# Droon_REV3.net
KiCad netlist of a schematic drawn in Altium Designer
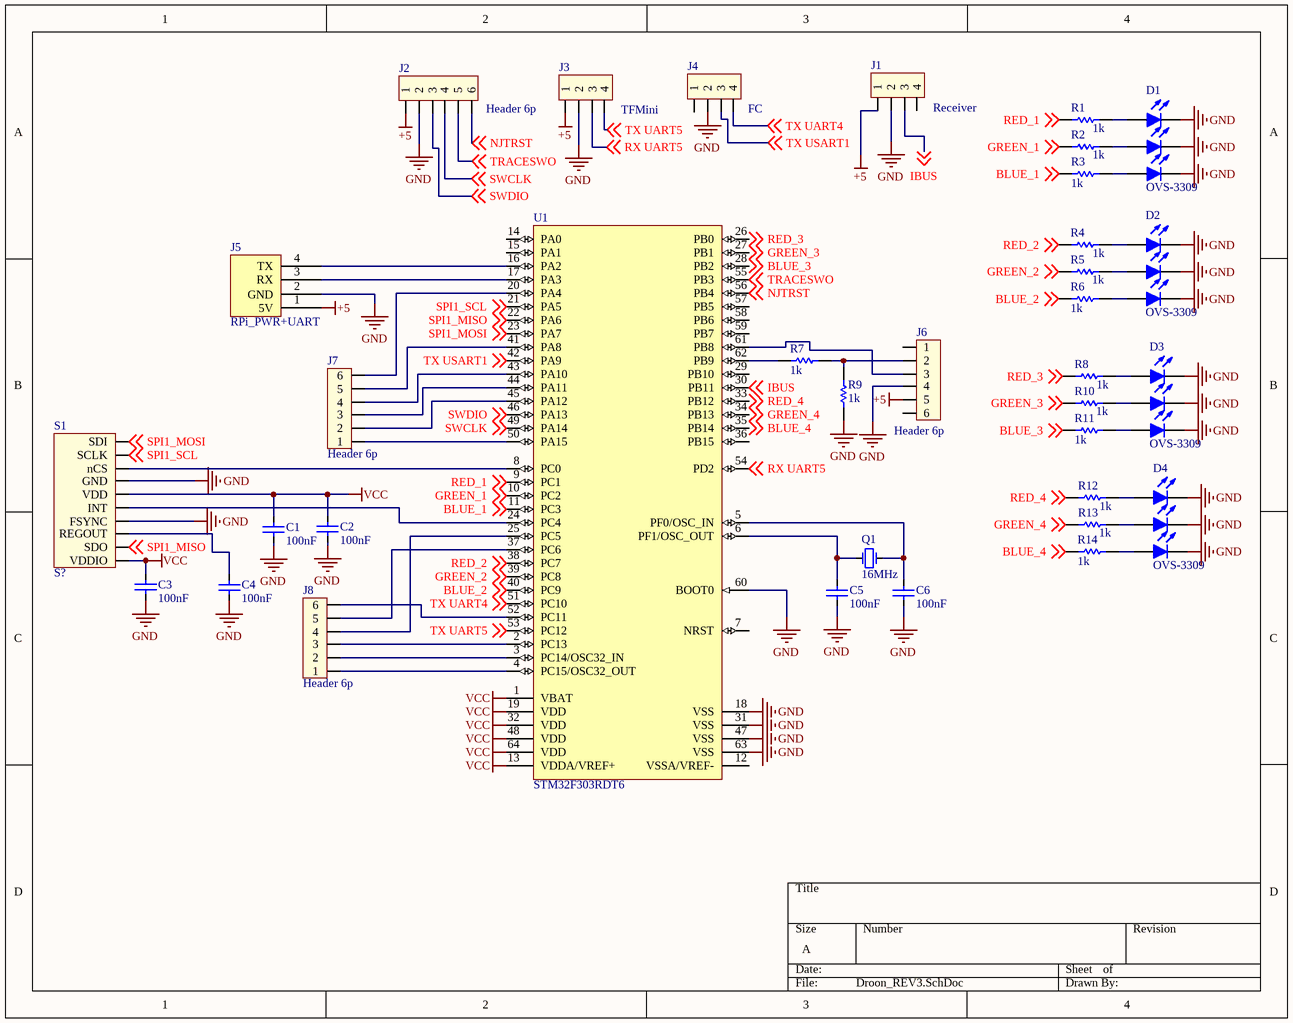
[diagram p0: Droon_REV3.SchDoc]

(export (version "E")
  (design (tool "Eeschema 10.0.6"))
  (components
    (comp (ref "C1")
      (value "100nF")
      (footprint "C0603")
      (description "Capacitor Ceramic")
      (libsource (lib "RK_Lib") (part "Capacitor"))
    )
    (comp (ref "C2")
      (value "100nF")
      (footprint "C0603")
      (description "Capacitor Ceramic")
      (libsource (lib "RK_Lib") (part "Capacitor"))
    )
    (comp (ref "C3")
      (value "100nF")
      (footprint "C0603")
      (description "Capacitor Ceramic")
      (libsource (lib "RK_Lib") (part "Capacitor"))
    )
    (comp (ref "C4")
      (value "100nF")
      (footprint "C0603")
      (description "Capacitor Ceramic")
      (libsource (lib "RK_Lib") (part "Capacitor"))
    )
    (comp (ref "C5")
      (value "100nF")
      (footprint "C0603")
      (description "Capacitor Ceramic")
      (libsource (lib "RK_Lib") (part "Capacitor"))
    )
    (comp (ref "C6")
      (value "100nF")
      (footprint "C0603")
      (description "Capacitor Ceramic")
      (libsource (lib "RK_Lib") (part "Capacitor"))
    )
    (comp (ref "D1")
      (value "OVS-3309")
      (footprint "LED RGB")
      (description "LED RGB")
      (libsource (lib "RK_Lib") (part "LED Tripple"))
    )
    (comp (ref "D2")
      (value "OVS-3309")
      (footprint "LED RGB")
      (description "LED RGB")
      (libsource (lib "RK_Lib") (part "LED Tripple"))
    )
    (comp (ref "D3")
      (value "OVS-3309")
      (footprint "LED RGB")
      (description "LED RGB")
      (libsource (lib "RK_Lib") (part "LED Tripple"))
    )
    (comp (ref "D4")
      (value "OVS-3309")
      (footprint "LED RGB")
      (description "LED RGB")
      (libsource (lib "RK_Lib") (part "LED Tripple"))
    )
    (comp (ref "J1")
      (value "Receiver")
      (footprint "JST-SH 4pin 1mm pitch")
      (libsource (lib "RK_Lib") (part "Header 4p"))
    )
    (comp (ref "J2")
      (value "Header 6p")
      (footprint "JST-SH 6pin 1mm pitch")
      (libsource (lib "") (part "Header 6p_2"))
    )
    (comp (ref "J3")
      (value "TFMini")
      (footprint "JST-SH 4pin 1mm pitch")
      (libsource (lib "RK_Lib") (part "Header 4p"))
    )
    (comp (ref "J4")
      (value "FC")
      (footprint "JST-SH 4pin 1mm pitch")
      (libsource (lib "RK_Lib") (part "Header 4p"))
    )
    (comp (ref "J5")
      (value "RPi_PWR+UART")
      (footprint "Header 2x20 2.54mm")
      (libsource (lib "RK_Lib") (part "RPi_PWR+UART"))
    )
    (comp (ref "J6")
      (value "Header 6p")
      (footprint "HEADER 6x1 2.54")
      (libsource (lib "") (part "Header 6p_3"))
    )
    (comp (ref "J7")
      (value "Header 6p")
      (footprint "JST-SH 6pin 1mm pitch")
      (libsource (lib "RK_Lib") (part "Header 6p"))
    )
    (comp (ref "J8")
      (value "Header 6p")
      (footprint "JST-SH 6pin 1mm pitch")
      (libsource (lib "") (part "Header 6p_1"))
    )
    (comp (ref "Q1")
      (value "16MHz")
      (footprint "Clock 2012\"(5032)")
      (description "Quarz crystal")
      (libsource (lib "RK_Lib") (part "Crystal"))
    )
    (comp (ref "R1")
      (value "1k")
      (footprint "R 0603")
      (description "Resistor")
      (libsource (lib "RK_Lib") (part "Res"))
    )
    (comp (ref "R2")
      (value "1k")
      (footprint "R 0603")
      (description "Resistor")
      (libsource (lib "RK_Lib") (part "Res"))
    )
    (comp (ref "R3")
      (value "1k")
      (footprint "R 0603")
      (description "Resistor")
      (libsource (lib "RK_Lib") (part "Res"))
    )
    (comp (ref "R4")
      (value "1k")
      (footprint "R 0603")
      (description "Resistor")
      (libsource (lib "RK_Lib") (part "Res"))
    )
    (comp (ref "R5")
      (value "1k")
      (footprint "R 0603")
      (description "Resistor")
      (libsource (lib "RK_Lib") (part "Res"))
    )
    (comp (ref "R6")
      (value "1k")
      (footprint "R 0603")
      (description "Resistor")
      (libsource (lib "RK_Lib") (part "Res"))
    )
    (comp (ref "R7")
      (value "1k")
      (footprint "R 0603")
      (description "Resistor")
      (libsource (lib "RK_Lib") (part "Res"))
    )
    (comp (ref "R8")
      (value "1k")
      (footprint "R 0603")
      (description "Resistor")
      (libsource (lib "RK_Lib") (part "Res"))
    )
    (comp (ref "R9")
      (value "1k")
      (footprint "R 0603")
      (description "Resistor")
      (libsource (lib "RK_Lib") (part "Res"))
    )
    (comp (ref "R10")
      (value "1k")
      (footprint "R 0603")
      (description "Resistor")
      (libsource (lib "RK_Lib") (part "Res"))
    )
    (comp (ref "R11")
      (value "1k")
      (footprint "R 0603")
      (description "Resistor")
      (libsource (lib "RK_Lib") (part "Res"))
    )
    (comp (ref "R12")
      (value "1k")
      (footprint "R 0603")
      (description "Resistor")
      (libsource (lib "RK_Lib") (part "Res"))
    )
    (comp (ref "R13")
      (value "1k")
      (footprint "R 0603")
      (description "Resistor")
      (libsource (lib "RK_Lib") (part "Res"))
    )
    (comp (ref "R14")
      (value "1k")
      (footprint "R 0603")
      (description "Resistor")
      (libsource (lib "RK_Lib") (part "Res"))
    )
    (comp (ref "S1")
      (value "S?")
      (footprint "IMU-ICM-20689")
      (libsource (lib "RK_Lib") (part "IMU_ICM-20689"))
    )
    (comp (ref "U1")
      (value "STM32F303RDT6")
      (footprint "LQFP64-STM32F303")
      (libsource (lib "RK_Lib") (part "LQFP64-STM32F303"))
    )
  )
  (nets
    (net (code "1") (name "+5") (class "Default")
      (node (ref "J1") (pin "1") (pinfunction "1_1") (pintype "passive"))
      (node (ref "J2") (pin "1") (pinfunction "1_1") (pintype "passive"))
      (node (ref "J3") (pin "1") (pinfunction "1_1") (pintype "passive"))
      (node (ref "J5") (pin "1") (pinfunction "5V_1") (pintype "passive"))
      (node (ref "J6") (pin "5") (pinfunction "5_5") (pintype "passive"))
    )
    (net (code "2") (name "BLUE_1") (class "Default")
      (node (ref "R3") (pin "1") (pinfunction "1_1") (pintype "passive"))
      (node (ref "U1") (pin "11") (pinfunction "PC3_11") (pintype "bidirectional"))
    )
    (net (code "3") (name "BLUE_2") (class "Default")
      (node (ref "R6") (pin "1") (pinfunction "1_1") (pintype "passive"))
      (node (ref "U1") (pin "40") (pinfunction "PC9_40") (pintype "bidirectional"))
    )
    (net (code "4") (name "BLUE_3") (class "Default")
      (node (ref "R11") (pin "1") (pinfunction "1_1") (pintype "passive"))
      (node (ref "U1") (pin "28") (pinfunction "PB2_28") (pintype "bidirectional"))
    )
    (net (code "5") (name "BLUE_4") (class "Default")
      (node (ref "R14") (pin "1") (pinfunction "1_1") (pintype "passive"))
      (node (ref "U1") (pin "35") (pinfunction "PB14_35") (pintype "bidirectional"))
    )
    (net (code "6") (name "GND") (class "Default")
      (node (ref "C1") (pin "1") (pinfunction "1_1") (pintype "passive"))
      (node (ref "C2") (pin "1") (pinfunction "1_1") (pintype "passive"))
      (node (ref "C3") (pin "1") (pinfunction "1_1") (pintype "passive"))
      (node (ref "C4") (pin "1") (pinfunction "1_1") (pintype "passive"))
      (node (ref "C5") (pin "1") (pinfunction "1_1") (pintype "passive"))
      (node (ref "C6") (pin "1") (pinfunction "1_1") (pintype "passive"))
      (node (ref "D1") (pin "BK") (pinfunction "BK_BK") (pintype "passive"))
      (node (ref "D1") (pin "GK") (pinfunction "GK_GK") (pintype "passive"))
      (node (ref "D1") (pin "RK") (pinfunction "RK_RK") (pintype "passive"))
      (node (ref "D2") (pin "BK") (pinfunction "BK_BK") (pintype "passive"))
      (node (ref "D2") (pin "GK") (pinfunction "GK_GK") (pintype "passive"))
      (node (ref "D2") (pin "RK") (pinfunction "RK_RK") (pintype "passive"))
      (node (ref "D3") (pin "BK") (pinfunction "BK_BK") (pintype "passive"))
      (node (ref "D3") (pin "GK") (pinfunction "GK_GK") (pintype "passive"))
      (node (ref "D3") (pin "RK") (pinfunction "RK_RK") (pintype "passive"))
      (node (ref "D4") (pin "BK") (pinfunction "BK_BK") (pintype "passive"))
      (node (ref "D4") (pin "GK") (pinfunction "GK_GK") (pintype "passive"))
      (node (ref "D4") (pin "RK") (pinfunction "RK_RK") (pintype "passive"))
      (node (ref "J1") (pin "2") (pinfunction "2_2") (pintype "passive"))
      (node (ref "J2") (pin "2") (pinfunction "2_2") (pintype "passive"))
      (node (ref "J3") (pin "2") (pinfunction "2_2") (pintype "passive"))
      (node (ref "J4") (pin "2") (pinfunction "2_2") (pintype "passive"))
      (node (ref "J5") (pin "2") (pinfunction "GND_2") (pintype "passive"))
      (node (ref "J6") (pin "4") (pinfunction "4_4") (pintype "passive"))
      (node (ref "R9") (pin "1") (pinfunction "1_1") (pintype "passive"))
      (node (ref "S1") (pin "11") (pinfunction "FSYNC_11") (pintype "passive"))
      (node (ref "S1") (pin "18") (pinfunction "GND_18") (pintype "passive"))
      (node (ref "U1") (pin "18") (pinfunction "VSS_18") (pintype "power_in"))
      (node (ref "U1") (pin "31") (pinfunction "VSS_31") (pintype "power_in"))
      (node (ref "U1") (pin "47") (pinfunction "VSS_47") (pintype "power_in"))
      (node (ref "U1") (pin "60") (pinfunction "BOOT0_60") (pintype "input"))
      (node (ref "U1") (pin "63") (pinfunction "VSS_63") (pintype "power_in"))
    )
    (net (code "7") (name "GREEN_1") (class "Default")
      (node (ref "R2") (pin "1") (pinfunction "1_1") (pintype "passive"))
      (node (ref "U1") (pin "10") (pinfunction "PC2_10") (pintype "bidirectional"))
    )
    (net (code "8") (name "GREEN_2") (class "Default")
      (node (ref "R5") (pin "1") (pinfunction "1_1") (pintype "passive"))
      (node (ref "U1") (pin "39") (pinfunction "PC8_39") (pintype "bidirectional"))
    )
    (net (code "9") (name "GREEN_3") (class "Default")
      (node (ref "R10") (pin "1") (pinfunction "1_1") (pintype "passive"))
      (node (ref "U1") (pin "27") (pinfunction "PB1_27") (pintype "bidirectional"))
    )
    (net (code "10") (name "GREEN_4") (class "Default")
      (node (ref "R13") (pin "1") (pinfunction "1_1") (pintype "passive"))
      (node (ref "U1") (pin "34") (pinfunction "PB13_34") (pintype "bidirectional"))
    )
    (net (code "11") (name "IBUS") (class "Default")
      (node (ref "J1") (pin "3") (pinfunction "3_3") (pintype "passive"))
      (node (ref "U1") (pin "30") (pinfunction "PB11_30") (pintype "bidirectional"))
    )
    (net (code "12") (name "NJTRST") (class "Default")
      (node (ref "J2") (pin "6") (pinfunction "6_6") (pintype "passive"))
      (node (ref "U1") (pin "56") (pinfunction "PB4_56") (pintype "bidirectional"))
    )
    (net (code "13") (name "Net-(D1-PadBA)") (class "Default")
      (node (ref "D1") (pin "BA") (pinfunction "BA_BA") (pintype "passive"))
      (node (ref "R3") (pin "2") (pinfunction "2_2") (pintype "passive"))
    )
    (net (code "14") (name "Net-(D1-PadGA)") (class "Default")
      (node (ref "D1") (pin "GA") (pinfunction "GA_GA") (pintype "passive"))
      (node (ref "R2") (pin "2") (pinfunction "2_2") (pintype "passive"))
    )
    (net (code "15") (name "Net-(D1-PadRA)") (class "Default")
      (node (ref "D1") (pin "RA") (pinfunction "RA_RA") (pintype "passive"))
      (node (ref "R1") (pin "2") (pinfunction "2_2") (pintype "passive"))
    )
    (net (code "16") (name "Net-(D2-PadBA)") (class "Default")
      (node (ref "D2") (pin "BA") (pinfunction "BA_BA") (pintype "passive"))
      (node (ref "R6") (pin "2") (pinfunction "2_2") (pintype "passive"))
    )
    (net (code "17") (name "Net-(D2-PadGA)") (class "Default")
      (node (ref "D2") (pin "GA") (pinfunction "GA_GA") (pintype "passive"))
      (node (ref "R5") (pin "2") (pinfunction "2_2") (pintype "passive"))
    )
    (net (code "18") (name "Net-(D2-PadRA)") (class "Default")
      (node (ref "D2") (pin "RA") (pinfunction "RA_RA") (pintype "passive"))
      (node (ref "R4") (pin "2") (pinfunction "2_2") (pintype "passive"))
    )
    (net (code "19") (name "Net-(D3-PadBA)") (class "Default")
      (node (ref "D3") (pin "BA") (pinfunction "BA_BA") (pintype "passive"))
      (node (ref "R11") (pin "2") (pinfunction "2_2") (pintype "passive"))
    )
    (net (code "20") (name "Net-(D3-PadGA)") (class "Default")
      (node (ref "D3") (pin "GA") (pinfunction "GA_GA") (pintype "passive"))
      (node (ref "R10") (pin "2") (pinfunction "2_2") (pintype "passive"))
    )
    (net (code "21") (name "Net-(D3-PadRA)") (class "Default")
      (node (ref "D3") (pin "RA") (pinfunction "RA_RA") (pintype "passive"))
      (node (ref "R8") (pin "2") (pinfunction "2_2") (pintype "passive"))
    )
    (net (code "22") (name "Net-(D4-PadBA)") (class "Default")
      (node (ref "D4") (pin "BA") (pinfunction "BA_BA") (pintype "passive"))
      (node (ref "R14") (pin "2") (pinfunction "2_2") (pintype "passive"))
    )
    (net (code "23") (name "Net-(D4-PadGA)") (class "Default")
      (node (ref "D4") (pin "GA") (pinfunction "GA_GA") (pintype "passive"))
      (node (ref "R13") (pin "2") (pinfunction "2_2") (pintype "passive"))
    )
    (net (code "24") (name "Net-(D4-PadRA)") (class "Default")
      (node (ref "D4") (pin "RA") (pinfunction "RA_RA") (pintype "passive"))
      (node (ref "R12") (pin "2") (pinfunction "2_2") (pintype "passive"))
    )
    (net (code "25") (name "Net-(J5-RX)") (class "Default")
      (node (ref "J5") (pin "3") (pinfunction "RX_3") (pintype "passive"))
      (node (ref "U1") (pin "17") (pinfunction "PA3_17") (pintype "bidirectional"))
    )
    (net (code "26") (name "Net-(J5-TX)") (class "Default")
      (node (ref "J5") (pin "4") (pinfunction "TX_4") (pintype "passive"))
      (node (ref "U1") (pin "16") (pinfunction "PA2_16") (pintype "bidirectional"))
    )
    (net (code "27") (name "Net-(J6-Pad2)") (class "Default")
      (node (ref "J6") (pin "2") (pinfunction "2_2") (pintype "passive"))
      (node (ref "R7") (pin "2") (pinfunction "2_2") (pintype "passive"))
      (node (ref "R9") (pin "2") (pinfunction "2_2") (pintype "passive"))
    )
    (net (code "28") (name "Net-(J7-1)") (class "Default")
      (node (ref "J7") (pin "6") (pinfunction "1_6") (pintype "passive"))
      (node (ref "U1") (pin "50") (pinfunction "PA15_50") (pintype "bidirectional"))
    )
    (net (code "29") (name "Net-(J7-2)") (class "Default")
      (node (ref "J7") (pin "5") (pinfunction "2_5") (pintype "passive"))
      (node (ref "U1") (pin "45") (pinfunction "PA12_45") (pintype "bidirectional"))
    )
    (net (code "30") (name "Net-(J7-3)") (class "Default")
      (node (ref "J7") (pin "4") (pinfunction "3_4") (pintype "passive"))
      (node (ref "U1") (pin "44") (pinfunction "PA11_44") (pintype "bidirectional"))
    )
    (net (code "31") (name "Net-(J7-4)") (class "Default")
      (node (ref "J7") (pin "3") (pinfunction "4_3") (pintype "passive"))
      (node (ref "U1") (pin "43") (pinfunction "PA10_43") (pintype "bidirectional"))
    )
    (net (code "32") (name "Net-(J7-5)") (class "Default")
      (node (ref "J7") (pin "2") (pinfunction "5_2") (pintype "passive"))
      (node (ref "U1") (pin "41") (pinfunction "PA8_41") (pintype "bidirectional"))
    )
    (net (code "33") (name "Net-(J7-6)") (class "Default")
      (node (ref "J7") (pin "1") (pinfunction "6_1") (pintype "passive"))
      (node (ref "U1") (pin "20") (pinfunction "PA4_20") (pintype "bidirectional"))
    )
    (net (code "34") (name "Net-(Q1-OSC1)") (class "Default")
      (node (ref "C5") (pin "2") (pinfunction "2_2") (pintype "passive"))
      (node (ref "Q1") (pin "1") (pinfunction "OSC1_1") (pintype "passive"))
      (node (ref "U1") (pin "6") (pinfunction "PF1/OSC_OUT_6") (pintype "bidirectional"))
    )
    (net (code "35") (name "Net-(Q1-OSC2)") (class "Default")
      (node (ref "C6") (pin "2") (pinfunction "2_2") (pintype "passive"))
      (node (ref "Q1") (pin "2") (pinfunction "OSC2_2") (pintype "passive"))
      (node (ref "U1") (pin "5") (pinfunction "PF0/OSC_IN_5") (pintype "bidirectional"))
    )
    (net (code "36") (name "Net-(S1-INT)") (class "Default")
      (node (ref "S1") (pin "12") (pinfunction "INT_12") (pintype "passive"))
      (node (ref "U1") (pin "24") (pinfunction "PC4_24") (pintype "bidirectional"))
    )
    (net (code "37") (name "Net-(S1-REGOUT)") (class "Default")
      (node (ref "C4") (pin "2") (pinfunction "2_2") (pintype "passive"))
      (node (ref "S1") (pin "10") (pinfunction "REGOUT_10") (pintype "passive"))
    )
    (net (code "38") (name "Net-(S1-nCS)") (class "Default")
      (node (ref "S1") (pin "22") (pinfunction "nCS_22") (pintype "passive"))
      (node (ref "U1") (pin "8") (pinfunction "PC0_8") (pintype "bidirectional"))
    )
    (net (code "39") (name "Net-(U1-PB8)") (class "Default")
      (node (ref "J6") (pin "3") (pinfunction "3_3") (pintype "passive"))
      (node (ref "U1") (pin "61") (pinfunction "PB8_61") (pintype "bidirectional"))
    )
    (net (code "40") (name "Net-(U1-PB9)") (class "Default")
      (node (ref "R7") (pin "1") (pinfunction "1_1") (pintype "passive"))
      (node (ref "U1") (pin "62") (pinfunction "PB9_62") (pintype "bidirectional"))
    )
    (net (code "41") (name "Net-(U1-PC5)") (class "Default")
      (node (ref "J8") (pin "4") (pinfunction "4_4") (pintype "passive"))
      (node (ref "U1") (pin "25") (pinfunction "PC5_25") (pintype "bidirectional"))
    )
    (net (code "42") (name "Net-(U1-PC6)") (class "Default")
      (node (ref "J8") (pin "5") (pinfunction "5_5") (pintype "passive"))
      (node (ref "U1") (pin "37") (pinfunction "PC6_37") (pintype "bidirectional"))
    )
    (net (code "43") (name "Net-(U1-PC11)") (class "Default")
      (node (ref "J8") (pin "6") (pinfunction "6_6") (pintype "passive"))
      (node (ref "U1") (pin "52") (pinfunction "PC11_52") (pintype "bidirectional"))
    )
    (net (code "44") (name "Net-(U1-PC13)") (class "Default")
      (node (ref "J8") (pin "3") (pinfunction "3_3") (pintype "passive"))
      (node (ref "U1") (pin "2") (pinfunction "PC13_2") (pintype "bidirectional"))
    )
    (net (code "45") (name "Net-(U1-PC14{slash}OSC32_IN)") (class "Default")
      (node (ref "J8") (pin "2") (pinfunction "2_2") (pintype "passive"))
      (node (ref "U1") (pin "3") (pinfunction "PC14/OSC32_IN_3") (pintype "bidirectional"))
    )
    (net (code "46") (name "Net-(U1-PC15{slash}OSC32_OUT)") (class "Default")
      (node (ref "J8") (pin "1") (pinfunction "1_1") (pintype "passive"))
      (node (ref "U1") (pin "4") (pinfunction "PC15/OSC32_OUT_4") (pintype "bidirectional"))
    )
    (net (code "47") (name "RED_1") (class "Default")
      (node (ref "R1") (pin "1") (pinfunction "1_1") (pintype "passive"))
      (node (ref "U1") (pin "9") (pinfunction "PC1_9") (pintype "bidirectional"))
    )
    (net (code "48") (name "RED_2") (class "Default")
      (node (ref "R4") (pin "1") (pinfunction "1_1") (pintype "passive"))
      (node (ref "U1") (pin "38") (pinfunction "PC7_38") (pintype "bidirectional"))
    )
    (net (code "49") (name "RED_3") (class "Default")
      (node (ref "R8") (pin "1") (pinfunction "1_1") (pintype "passive"))
      (node (ref "U1") (pin "26") (pinfunction "PB0_26") (pintype "bidirectional"))
    )
    (net (code "50") (name "RED_4") (class "Default")
      (node (ref "R12") (pin "1") (pinfunction "1_1") (pintype "passive"))
      (node (ref "U1") (pin "33") (pinfunction "PB12_33") (pintype "bidirectional"))
    )
    (net (code "51") (name "RX UART5") (class "Default")
      (node (ref "J3") (pin "3") (pinfunction "3_3") (pintype "passive"))
      (node (ref "U1") (pin "54") (pinfunction "PD2_54") (pintype "bidirectional"))
    )
    (net (code "52") (name "SPI1_MISO") (class "Default")
      (node (ref "S1") (pin "9") (pinfunction "SDO_9") (pintype "passive"))
      (node (ref "U1") (pin "22") (pinfunction "PA6_22") (pintype "bidirectional"))
    )
    (net (code "53") (name "SPI1_MOSI") (class "Default")
      (node (ref "S1") (pin "24") (pinfunction "SDI_24") (pintype "passive"))
      (node (ref "U1") (pin "23") (pinfunction "PA7_23") (pintype "bidirectional"))
    )
    (net (code "54") (name "SPI1_SCL") (class "Default")
      (node (ref "S1") (pin "23") (pinfunction "SCLK_23") (pintype "passive"))
      (node (ref "U1") (pin "21") (pinfunction "PA5_21") (pintype "bidirectional"))
    )
    (net (code "55") (name "SWCLK") (class "Default")
      (node (ref "J2") (pin "4") (pinfunction "4_4") (pintype "passive"))
      (node (ref "U1") (pin "49") (pinfunction "PA14_49") (pintype "bidirectional"))
    )
    (net (code "56") (name "SWDIO") (class "Default")
      (node (ref "J2") (pin "3") (pinfunction "3_3") (pintype "passive"))
      (node (ref "U1") (pin "46") (pinfunction "PA13_46") (pintype "bidirectional"))
    )
    (net (code "57") (name "TRACESWO") (class "Default")
      (node (ref "J2") (pin "5") (pinfunction "5_5") (pintype "passive"))
      (node (ref "U1") (pin "55") (pinfunction "PB3_55") (pintype "bidirectional"))
    )
    (net (code "58") (name "TX UART4") (class "Default")
      (node (ref "J4") (pin "4") (pinfunction "4_4") (pintype "passive"))
      (node (ref "U1") (pin "51") (pinfunction "PC10_51") (pintype "bidirectional"))
    )
    (net (code "59") (name "TX UART5") (class "Default")
      (node (ref "J3") (pin "4") (pinfunction "4_4") (pintype "passive"))
      (node (ref "U1") (pin "53") (pinfunction "PC12_53") (pintype "bidirectional"))
    )
    (net (code "60") (name "TX USART1") (class "Default")
      (node (ref "J4") (pin "3") (pinfunction "3_3") (pintype "passive"))
      (node (ref "U1") (pin "42") (pinfunction "PA9_42") (pintype "bidirectional"))
    )
    (net (code "61") (name "VCC") (class "Default")
      (node (ref "C1") (pin "2") (pinfunction "2_2") (pintype "passive"))
      (node (ref "C2") (pin "2") (pinfunction "2_2") (pintype "passive"))
      (node (ref "C3") (pin "2") (pinfunction "2_2") (pintype "passive"))
      (node (ref "S1") (pin "13") (pinfunction "VDD_13") (pintype "passive"))
      (node (ref "S1") (pin "8") (pinfunction "VDDIO_8") (pintype "passive"))
      (node (ref "U1") (pin "1") (pinfunction "VBAT_1") (pintype "power_in"))
      (node (ref "U1") (pin "13") (pinfunction "VDDA/VREF+_13") (pintype "power_in"))
      (node (ref "U1") (pin "19") (pinfunction "VDD_19") (pintype "power_in"))
      (node (ref "U1") (pin "32") (pinfunction "VDD_32") (pintype "power_in"))
      (node (ref "U1") (pin "48") (pinfunction "VDD_48") (pintype "power_in"))
      (node (ref "U1") (pin "64") (pinfunction "VDD_64") (pintype "power_in"))
    )
    (net (code "62") (name "unconnected-(J1-Pad4)") (class "Default")
      (node (ref "J1") (pin "4") (pinfunction "4_4") (pintype "passive"))
    )
    (net (code "63") (name "unconnected-(J4-Pad1)") (class "Default")
      (node (ref "J4") (pin "1") (pinfunction "1_1") (pintype "passive"))
    )
    (net (code "64") (name "unconnected-(J6-Pad1)") (class "Default")
      (node (ref "J6") (pin "1") (pinfunction "1_1") (pintype "passive"))
    )
    (net (code "65") (name "unconnected-(J6-Pad6)") (class "Default")
      (node (ref "J6") (pin "6") (pinfunction "6_6") (pintype "passive"))
    )
    (net (code "66") (name "unconnected-(U1-NRST-Pad7)") (class "Default")
      (node (ref "U1") (pin "7") (pinfunction "NRST_7") (pintype "bidirectional"))
    )
    (net (code "67") (name "unconnected-(U1-PA0-Pad14)") (class "Default")
      (node (ref "U1") (pin "14") (pinfunction "PA0_14") (pintype "bidirectional"))
    )
    (net (code "68") (name "unconnected-(U1-PA1-Pad15)") (class "Default")
      (node (ref "U1") (pin "15") (pinfunction "PA1_15") (pintype "bidirectional"))
    )
    (net (code "69") (name "unconnected-(U1-PB5-Pad57)") (class "Default")
      (node (ref "U1") (pin "57") (pinfunction "PB5_57") (pintype "bidirectional"))
    )
    (net (code "70") (name "unconnected-(U1-PB6-Pad58)") (class "Default")
      (node (ref "U1") (pin "58") (pinfunction "PB6_58") (pintype "bidirectional"))
    )
    (net (code "71") (name "unconnected-(U1-PB7-Pad59)") (class "Default")
      (node (ref "U1") (pin "59") (pinfunction "PB7_59") (pintype "bidirectional"))
    )
    (net (code "72") (name "unconnected-(U1-PB10-Pad29)") (class "Default")
      (node (ref "U1") (pin "29") (pinfunction "PB10_29") (pintype "bidirectional"))
    )
    (net (code "73") (name "unconnected-(U1-PB15-Pad36)") (class "Default")
      (node (ref "U1") (pin "36") (pinfunction "PB15_36") (pintype "bidirectional"))
    )
    (net (code "74") (name "unconnected-(U1-VSSA{slash}VREF--Pad12)") (class "Default")
      (node (ref "U1") (pin "12") (pinfunction "VSSA/VREF-_12") (pintype "power_in"))
    )
  )
)
